# Xino_RF_v1_3.net
KiCad netlist of a schematic drawn in EAGLE
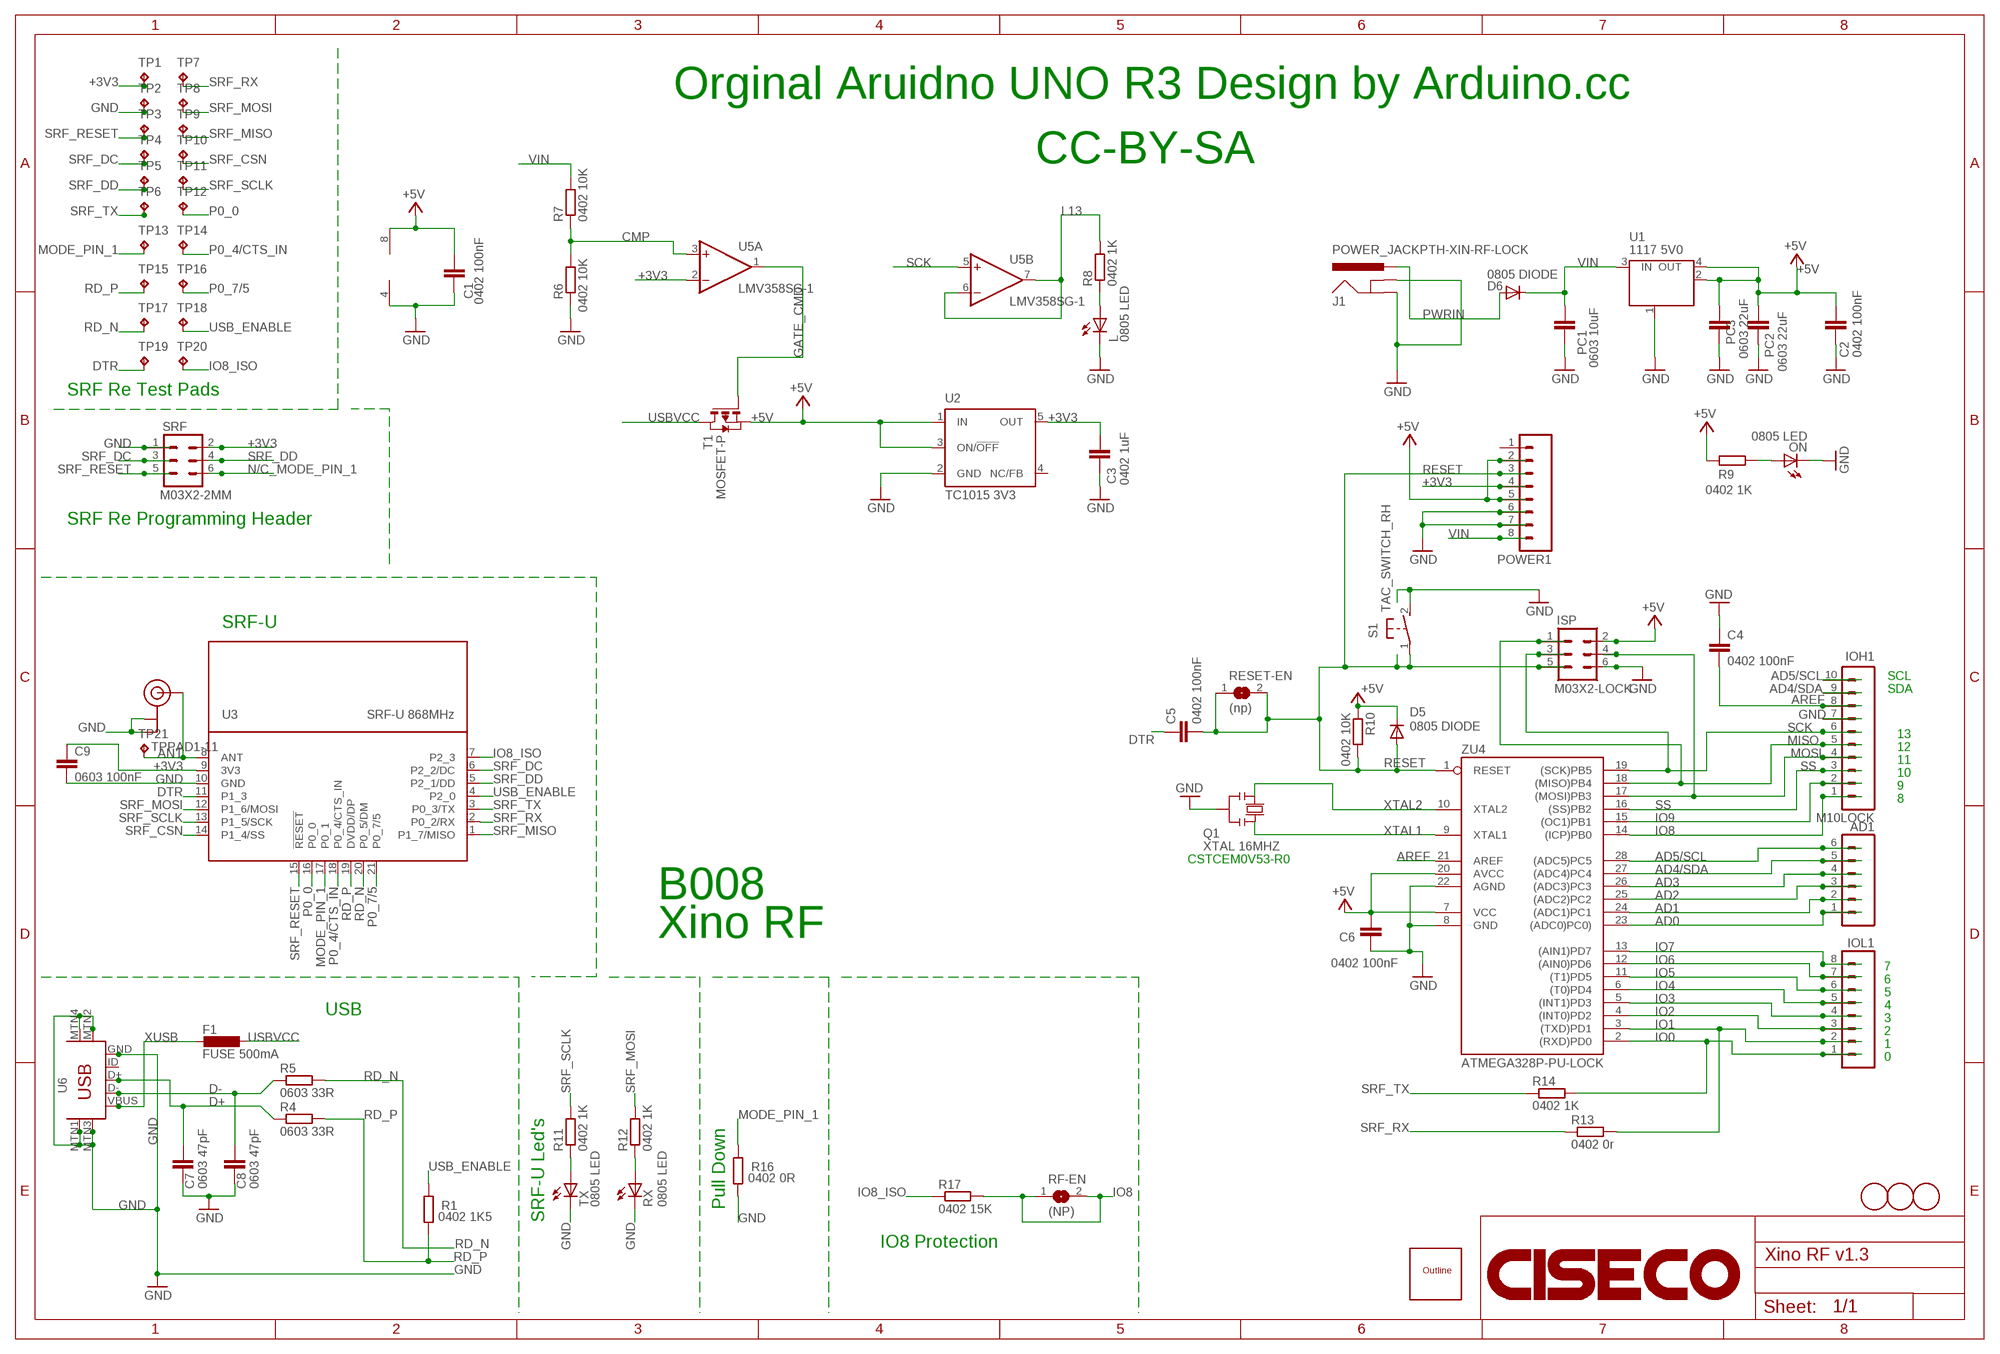
[diagram p0: schematic, sheet 1]

(export (version "E")
  (design (tool "Eeschema 10.0.6"))
  (components
    (comp (ref "AD1")
      (value "M06LOCK")
      (footprint "eagle-import:1X06_LOCK")
      (libsource (lib "eagle-import") (part "M06LOCK"))
    )
    (comp (ref "C1")
      (value "0402 100nF")
      (footprint "eagle-import:C0402-SMALLER")
      (libsource (lib "eagle-import") (part "C-EUC0402-SMALLER"))
    )
    (comp (ref "C2")
      (value "0402 100nF")
      (footprint "eagle-import:C0402-SMALLER")
      (libsource (lib "eagle-import") (part "C-EUC0402-SMALLER"))
    )
    (comp (ref "C3")
      (value "0402 1uF")
      (footprint "eagle-import:C0402-SMALLER")
      (libsource (lib "eagle-import") (part "C-EUC0402-SMALLER"))
    )
    (comp (ref "C4")
      (value "0402 100nF")
      (footprint "eagle-import:C0402-SMALLER")
      (libsource (lib "eagle-import") (part "C-EUC0402-SMALLER"))
    )
    (comp (ref "C5")
      (value "0402 100nF")
      (footprint "eagle-import:C0402-SMALLER")
      (libsource (lib "eagle-import") (part "C-EUC0402-SMALLER"))
    )
    (comp (ref "C6")
      (value "0402 100nF")
      (footprint "eagle-import:C0603-ROUND")
      (libsource (lib "eagle-import") (part "C-EU0603-RND"))
    )
    (comp (ref "C7")
      (value "0603 47pF")
      (footprint "eagle-import:C0603K-SMALL")
      (libsource (lib "eagle-import") (part "C-EUC0603K-SMALL"))
    )
    (comp (ref "C8")
      (value "0603 47pF")
      (footprint "eagle-import:C0603K-SMALL")
      (libsource (lib "eagle-import") (part "C-EUC0603K-SMALL"))
    )
    (comp (ref "C9")
      (value "0603 100nF")
      (footprint "eagle-import:C0402-SMALLER")
      (libsource (lib "eagle-import") (part "C-EUC0402-SMALLER"))
    )
    (comp (ref "D5")
      (value "0805 DIODE")
      (footprint "eagle-import:0805-DIODE")
      (libsource (lib "eagle-import") (part "DIODE-0805"))
    )
    (comp (ref "D6")
      (value "0805 DIODE")
      (footprint "eagle-import:0805-DIODE")
      (libsource (lib "eagle-import") (part "DIODE-0805"))
    )
    (comp (ref "F1")
      (value "FUSE 500mA")
      (footprint "eagle-import:L1812")
      (libsource (lib "eagle-import") (part "L-EUL1812"))
    )
    (comp (ref "FD1")
      (value "FIDUCIALMOUNT")
      (footprint "eagle-import:FIDUCIA-MOUNT")
      (libsource (lib "eagle-import") (part "FIDUCIALMOUNT"))
    )
    (comp (ref "FD2")
      (value "FIDUCIALMOUNT")
      (footprint "eagle-import:FIDUCIA-MOUNT")
      (libsource (lib "eagle-import") (part "FIDUCIALMOUNT"))
    )
    (comp (ref "FD3")
      (value "FIDUCIALMOUNT")
      (footprint "eagle-import:FIDUCIA-MOUNT")
      (libsource (lib "eagle-import") (part "FIDUCIALMOUNT"))
    )
    (comp (ref "IOH1")
      (value "M10LOCK")
      (footprint "eagle-import:1X10_LOCK")
      (libsource (lib "eagle-import") (part "M10LOCK"))
    )
    (comp (ref "IOL1")
      (value "M08LOCK")
      (footprint "eagle-import:1X08_LOCK")
      (libsource (lib "eagle-import") (part "M08LOCK"))
    )
    (comp (ref "ISP")
      (value "M03X2-LOCK")
      (footprint "eagle-import:2X3_LOCK")
      (libsource (lib "eagle-import") (part "M03X2-LOCK"))
    )
    (comp (ref "J1")
      (value "POWER_JACKPTH-XIN-RF-LOCK")
      (footprint "eagle-import:POWER_JACK_PTH_XINO_RF_LOCK")
      (libsource (lib "eagle-import") (part "POWER_JACKPTH-XIN-RF-LOCK"))
    )
    (comp (ref "L")
      (value "0805 LED")
      (footprint "eagle-import:LED-0805-1206")
      (libsource (lib "eagle-import") (part "LED0805-1206"))
    )
    (comp (ref "ON")
      (value "0805 LED")
      (footprint "eagle-import:LED-0805-1206")
      (libsource (lib "eagle-import") (part "LED0805-1206"))
    )
    (comp (ref "PC1")
      (value "0603 10uF")
      (footprint "eagle-import:C0805K")
      (libsource (lib "eagle-import") (part "C-EUC0805K"))
    )
    (comp (ref "PC2")
      (value "0603 22uF")
      (footprint "eagle-import:C0805K")
      (libsource (lib "eagle-import") (part "C-EUC0805K"))
    )
    (comp (ref "PC3")
      (value "0603 22uF")
      (footprint "eagle-import:C0805K")
      (libsource (lib "eagle-import") (part "C-EUC0805K"))
    )
    (comp (ref "POWER1")
      (value "M08LOCK")
      (footprint "eagle-import:1X08_LOCK")
      (libsource (lib "eagle-import") (part "M08LOCK"))
    )
    (comp (ref "Q1")
      (value "XTAL 16MHZ")
      (footprint "eagle-import:RESONATOR")
      (libsource (lib "eagle-import") (part "RESONATORMU"))
    )
    (comp (ref "R1")
      (value "0402 1K5")
      (footprint "eagle-import:R0402-SMALLER")
      (libsource (lib "eagle-import") (part "R-EU_R0402-SMALLER"))
    )
    (comp (ref "R4")
      (value "0603 33R")
      (footprint "eagle-import:C0603K-SMALL")
      (libsource (lib "eagle-import") (part "R-EU_0603K-SMALL"))
    )
    (comp (ref "R5")
      (value "0603 33R")
      (footprint "eagle-import:C0603K-SMALL")
      (libsource (lib "eagle-import") (part "R-EU_0603K-SMALL"))
    )
    (comp (ref "R6")
      (value "0402 10K")
      (footprint "eagle-import:R0402-SMALLER")
      (libsource (lib "eagle-import") (part "R-EU_R0402-SMALLER"))
    )
    (comp (ref "R7")
      (value "0402 10K")
      (footprint "eagle-import:R0402-SMALLER")
      (libsource (lib "eagle-import") (part "R-EU_R0402-SMALLER"))
    )
    (comp (ref "R8")
      (value "0402 1K")
      (footprint "eagle-import:R0402-SMALLER")
      (libsource (lib "eagle-import") (part "R-EU_R0402-SMALLER"))
    )
    (comp (ref "R9")
      (value "0402 1K")
      (footprint "eagle-import:R0402-SMALLER")
      (libsource (lib "eagle-import") (part "R-EU_R0402-SMALLER"))
    )
    (comp (ref "R10")
      (value "0402 10K")
      (footprint "eagle-import:R0402-SMALLER")
      (libsource (lib "eagle-import") (part "R-EU_R0402-SMALLER"))
    )
    (comp (ref "R11")
      (value "0402 1K")
      (footprint "eagle-import:R0402-SMALLER")
      (libsource (lib "eagle-import") (part "R-EU_R0402-SMALLER"))
    )
    (comp (ref "R12")
      (value "0402 1K")
      (footprint "eagle-import:R0402-SMALLER")
      (libsource (lib "eagle-import") (part "R-EU_R0402-SMALLER"))
    )
    (comp (ref "R13")
      (value "0402 0r")
      (footprint "eagle-import:R0402-SMALLER")
      (libsource (lib "eagle-import") (part "R-EU_R0402-SMALLER"))
    )
    (comp (ref "R14")
      (value "0402 1K")
      (footprint "eagle-import:R0402-SMALLER")
      (libsource (lib "eagle-import") (part "R-EU_R0402-SMALLER"))
    )
    (comp (ref "R16")
      (value "0402 0R")
      (footprint "eagle-import:R0402-SMALLER")
      (libsource (lib "eagle-import") (part "R-EU_R0402-SMALLER"))
    )
    (comp (ref "R17")
      (value "0402 15K")
      (footprint "eagle-import:R0402-SMALLER")
      (libsource (lib "eagle-import") (part "R-EU_R0402-SMALLER"))
    )
    (comp (ref "RESET-EN")
      (value "(np)")
      (footprint "eagle-import:SJ")
      (libsource (lib "eagle-import") (part "SJ"))
    )
    (comp (ref "RF-EN")
      (value "(NP)")
      (footprint "eagle-import:SJ")
      (libsource (lib "eagle-import") (part "SJ"))
    )
    (comp (ref "RX")
      (value "0805 LED")
      (footprint "eagle-import:LED-0805-1206")
      (libsource (lib "eagle-import") (part "LED0805-1206"))
    )
    (comp (ref "S1")
      (value "TAC_SWITCH_RH")
      (footprint "eagle-import:B3F-31XX")
      (libsource (lib "eagle-import") (part "TAC_SWITCH_RH"))
    )
    (comp (ref "SRF")
      (value "M03X2-2MM")
      (footprint "eagle-import:2X3_2MM")
      (libsource (lib "eagle-import") (part "M03X2-2MM"))
    )
    (comp (ref "T1")
      (value "MOSFET-P")
      (footprint "eagle-import:SOT-23")
      (libsource (lib "eagle-import") (part "PMOSSOT23"))
    )
    (comp (ref "TP1")
      (value "TPB1,27")
      (footprint "eagle-import:B1,27")
      (libsource (lib "eagle-import") (part "testpad_TPB1,27"))
    )
    (comp (ref "TP2")
      (value "TPB1,27")
      (footprint "eagle-import:B1,27")
      (libsource (lib "eagle-import") (part "testpad_TPB1,27"))
    )
    (comp (ref "TP3")
      (value "TPB1,27")
      (footprint "eagle-import:B1,27")
      (libsource (lib "eagle-import") (part "testpad_TPB1,27"))
    )
    (comp (ref "TP4")
      (value "TPB1,27")
      (footprint "eagle-import:B1,27")
      (libsource (lib "eagle-import") (part "testpad_TPB1,27"))
    )
    (comp (ref "TP5")
      (value "TPB1,27")
      (footprint "eagle-import:B1,27")
      (libsource (lib "eagle-import") (part "testpad_TPB1,27"))
    )
    (comp (ref "TP6")
      (value "TPB1,27")
      (footprint "eagle-import:B1,27")
      (libsource (lib "eagle-import") (part "testpad_TPB1,27"))
    )
    (comp (ref "TP7")
      (value "TPB1,27")
      (footprint "eagle-import:B1,27")
      (libsource (lib "eagle-import") (part "testpad_TPB1,27"))
    )
    (comp (ref "TP8")
      (value "TPB1,27")
      (footprint "eagle-import:B1,27")
      (libsource (lib "eagle-import") (part "testpad_TPB1,27"))
    )
    (comp (ref "TP9")
      (value "TPB1,27")
      (footprint "eagle-import:B1,27")
      (libsource (lib "eagle-import") (part "testpad_TPB1,27"))
    )
    (comp (ref "TP10")
      (value "TPB1,27")
      (footprint "eagle-import:B1,27")
      (libsource (lib "eagle-import") (part "testpad_TPB1,27"))
    )
    (comp (ref "TP11")
      (value "TPB1,27")
      (footprint "eagle-import:B1,27")
      (libsource (lib "eagle-import") (part "testpad_TPB1,27"))
    )
    (comp (ref "TP12")
      (value "TPB1,27")
      (footprint "eagle-import:B1,27")
      (libsource (lib "eagle-import") (part "testpad_TPB1,27"))
    )
    (comp (ref "TP13")
      (value "TPB1,27")
      (footprint "eagle-import:B1,27")
      (libsource (lib "eagle-import") (part "testpad_TPB1,27"))
    )
    (comp (ref "TP14")
      (value "TPB1,27")
      (footprint "eagle-import:B1,27")
      (libsource (lib "eagle-import") (part "testpad_TPB1,27"))
    )
    (comp (ref "TP15")
      (value "TPB1,27")
      (footprint "eagle-import:B1,27")
      (libsource (lib "eagle-import") (part "testpad_TPB1,27"))
    )
    (comp (ref "TP16")
      (value "TPB1,27")
      (footprint "eagle-import:B1,27")
      (libsource (lib "eagle-import") (part "testpad_TPB1,27"))
    )
    (comp (ref "TP17")
      (value "TPB1,27")
      (footprint "eagle-import:B1,27")
      (libsource (lib "eagle-import") (part "testpad_TPB1,27"))
    )
    (comp (ref "TP18")
      (value "TPB1,27")
      (footprint "eagle-import:B1,27")
      (libsource (lib "eagle-import") (part "testpad_TPB1,27"))
    )
    (comp (ref "TP19")
      (value "TPB1,27")
      (footprint "eagle-import:B1,27")
      (libsource (lib "eagle-import") (part "testpad_TPB1,27"))
    )
    (comp (ref "TP20")
      (value "TPB1,27")
      (footprint "eagle-import:B1,27")
      (libsource (lib "eagle-import") (part "testpad_TPB1,27"))
    )
    (comp (ref "TP21")
      (value "TPPAD1-11")
      (footprint "eagle-import:P1-11")
      (libsource (lib "eagle-import") (part "TPPAD1-11"))
    )
    (comp (ref "TX")
      (value "0805 LED")
      (footprint "eagle-import:LED-0805-1206")
      (libsource (lib "eagle-import") (part "LED0805-1206"))
    )
    (comp (ref "U$1")
      (value "CISECO-MEDIUM")
      (footprint "eagle-import:CISECO-1.3MM")
      (libsource (lib "eagle-import") (part "CISECO-MEDIUM"))
    )
    (comp (ref "U$2")
      (value "ARDUINO-OUTLINE-MILL")
      (footprint "eagle-import:ARDUINO-OUTLINE-MILL")
      (libsource (lib "eagle-import") (part "ARDUINO-OUTLINE-MILL"))
    )
    (comp (ref "U$3")
      (value "CISECO-LARGE")
      (footprint "eagle-import:CISECO-4MM")
      (libsource (lib "eagle-import") (part "CISECO-LARGE"))
    )
    (comp (ref "U1")
      (value "1117 5V0")
      (footprint "eagle-import:SOT223")
      (libsource (lib "eagle-import") (part "MC33269ST-3.3T3"))
    )
    (comp (ref "U2")
      (value "TC1015 3V3")
      (footprint "eagle-import:SOT23-DBV")
      (libsource (lib "eagle-import") (part "LP2985-XXDBVR33"))
    )
    (comp (ref "U3")
      (value "SRF-U 868MHz")
      (footprint "eagle-import:SRF-LANDING-1.2")
      (libsource (lib "eagle-import") (part "SRF-LANDING-1.2"))
    )
    (comp (ref "U5")
      (value "LMV358SG-1")
      (footprint "eagle-import:SO08")
      (libsource (lib "eagle-import") (part "LMV358?MX"))
    )
    (comp (ref "U6")
      (value "USB-MINIB-5PIN")
      (footprint "eagle-import:USB-MINIB-CISECO-1")
      (libsource (lib "eagle-import") (part "USB-MINIB-5PIN-TWEAKED"))
    )
    (comp (ref "U11")
      (value "U.FL 868")
      (footprint "eagle-import:U.FL")
      (libsource (lib "eagle-import") (part "U.FL"))
    )
    (comp (ref "ZU4")
      (value "ATMEGA328P-PU-LOCK")
      (footprint "eagle-import:DIL28-3-LOCK")
      (libsource (lib "eagle-import") (part "ATMEGA328P-PU-LOCK"))
    )
  )
  (nets
    (net (code "1") (name "+5V") (class "Default")
      (node (ref "C1") (pin "2") (pinfunction "2_2") (pintype "passive"))
      (node (ref "C2") (pin "2") (pinfunction "2_2") (pintype "passive"))
      (node (ref "C6") (pin "2") (pinfunction "2_2") (pintype "passive"))
      (node (ref "D5") (pin "C") (pinfunction "C_C") (pintype "passive"))
      (node (ref "ISP") (pin "2") (pinfunction "2_2") (pintype "passive"))
      (node (ref "PC2") (pin "1") (pinfunction "1_1") (pintype "passive"))
      (node (ref "PC3") (pin "1") (pinfunction "1_1") (pintype "passive"))
      (node (ref "POWER1") (pin "2") (pinfunction "2_2") (pintype "passive"))
      (node (ref "POWER1") (pin "5") (pinfunction "5_5") (pintype "passive"))
      (node (ref "R10") (pin "1") (pinfunction "1_1") (pintype "passive"))
      (node (ref "R9") (pin "2") (pinfunction "2_2") (pintype "passive"))
      (node (ref "T1") (pin "2") (pinfunction "S_2") (pintype "passive"))
      (node (ref "U1") (pin "2") (pinfunction "OUT_2") (pintype "passive"))
      (node (ref "U1") (pin "4") (pinfunction "OUT_4") (pintype "passive"))
      (node (ref "U2") (pin "1") (pinfunction "IN_1") (pintype "input"))
      (node (ref "U2") (pin "3") (pinfunction "ON/~{OFF}_3") (pintype "input"))
      (node (ref "U5") (pin "8") (pinfunction "V+_8") (pintype "power_in"))
      (node (ref "ZU4") (pin "20") (pinfunction "AVCC_20") (pintype "power_in"))
      (node (ref "ZU4") (pin "7") (pinfunction "VCC_7") (pintype "power_in"))
    )
    (net (code "2") (name "/+3V3") (class "Default")
      (node (ref "C3") (pin "2") (pinfunction "2_2") (pintype "passive"))
      (node (ref "C9") (pin "1") (pinfunction "1_1") (pintype "passive"))
      (node (ref "POWER1") (pin "4") (pinfunction "4_4") (pintype "passive"))
      (node (ref "SRF") (pin "2") (pinfunction "2_2") (pintype "passive"))
      (node (ref "TP1") (pin "TP") (pinfunction "TP_TP") (pintype "input"))
      (node (ref "U2") (pin "5") (pinfunction "OUT_5") (pintype "passive"))
      (node (ref "U3") (pin "9") (pinfunction "3V3_9") (pintype "power_in"))
      (node (ref "U5") (pin "2") (pinfunction "-IN_2") (pintype "input"))
    )
    (net (code "3") (name "/AD0") (class "Default")
      (node (ref "AD1") (pin "1") (pinfunction "1_1") (pintype "passive"))
      (node (ref "ZU4") (pin "23") (pinfunction "(ADC0)PC0)_23") (pintype "bidirectional"))
    )
    (net (code "4") (name "/AD1") (class "Default")
      (node (ref "AD1") (pin "2") (pinfunction "2_2") (pintype "passive"))
      (node (ref "ZU4") (pin "24") (pinfunction "(ADC1)PC1_24") (pintype "bidirectional"))
    )
    (net (code "5") (name "/AD2") (class "Default")
      (node (ref "AD1") (pin "3") (pinfunction "3_3") (pintype "passive"))
      (node (ref "ZU4") (pin "25") (pinfunction "(ADC2)PC2_25") (pintype "bidirectional"))
    )
    (net (code "6") (name "/AD3") (class "Default")
      (node (ref "AD1") (pin "4") (pinfunction "4_4") (pintype "passive"))
      (node (ref "ZU4") (pin "26") (pinfunction "(ADC3)PC3_26") (pintype "bidirectional"))
    )
    (net (code "7") (name "/AD4{slash}SDA") (class "Default")
      (node (ref "AD1") (pin "5") (pinfunction "5_5") (pintype "passive"))
      (node (ref "IOH1") (pin "9") (pinfunction "9_9") (pintype "passive"))
      (node (ref "ZU4") (pin "27") (pinfunction "(ADC4)PC4_27") (pintype "bidirectional"))
    )
    (net (code "8") (name "/AD5{slash}SCL") (class "Default")
      (node (ref "AD1") (pin "6") (pinfunction "6_6") (pintype "passive"))
      (node (ref "IOH1") (pin "10") (pinfunction "10_10") (pintype "passive"))
      (node (ref "ZU4") (pin "28") (pinfunction "(ADC5)PC5_28") (pintype "bidirectional"))
    )
    (net (code "9") (name "/ANT") (class "Default")
      (node (ref "TP21") (pin "TP") (pinfunction "TP_TP") (pintype "input"))
      (node (ref "U11") (pin "P$3") (pinfunction "SIGNAL_P$3") (pintype "bidirectional"))
      (node (ref "U3") (pin "8") (pinfunction "ANT_8") (pintype "output"))
    )
    (net (code "10") (name "/AREF") (class "Default")
      (node (ref "C4") (pin "2") (pinfunction "2_2") (pintype "passive"))
      (node (ref "IOH1") (pin "8") (pinfunction "8_8") (pintype "passive"))
      (node (ref "ZU4") (pin "21") (pinfunction "AREF_21") (pintype "passive"))
    )
    (net (code "11") (name "/CMP") (class "Default")
      (node (ref "R6") (pin "2") (pinfunction "2_2") (pintype "passive"))
      (node (ref "R7") (pin "1") (pinfunction "1_1") (pintype "passive"))
      (node (ref "U5") (pin "3") (pinfunction "+IN_3") (pintype "input"))
    )
    (net (code "12") (name "/D+") (class "Default")
      (node (ref "C7") (pin "1") (pinfunction "1_1") (pintype "passive"))
      (node (ref "R4") (pin "1") (pinfunction "1_1") (pintype "passive"))
      (node (ref "U6") (pin "D+") (pinfunction "D+_D+") (pintype "bidirectional"))
    )
    (net (code "13") (name "/D-") (class "Default")
      (node (ref "C8") (pin "1") (pinfunction "1_1") (pintype "passive"))
      (node (ref "R5") (pin "1") (pinfunction "1_1") (pintype "passive"))
      (node (ref "U6") (pin "D-") (pinfunction "D-_D-") (pintype "bidirectional"))
    )
    (net (code "14") (name "/DTR") (class "Default")
      (node (ref "C5") (pin "1") (pinfunction "1_1") (pintype "passive"))
      (node (ref "TP19") (pin "TP") (pinfunction "TP_TP") (pintype "input"))
      (node (ref "U3") (pin "11") (pinfunction "P1_3_11") (pintype "bidirectional"))
    )
    (net (code "15") (name "/GATE_CMD") (class "Default")
      (node (ref "T1") (pin "3") (pinfunction "G_3") (pintype "passive"))
      (node (ref "U5") (pin "1") (pinfunction "OUT_1") (pintype "output"))
    )
    (net (code "16") (name "/IO0") (class "Default")
      (node (ref "IOL1") (pin "1") (pinfunction "1_1") (pintype "passive"))
      (node (ref "R14") (pin "2") (pinfunction "2_2") (pintype "passive"))
      (node (ref "ZU4") (pin "2") (pinfunction "(RXD)PD0_2") (pintype "bidirectional"))
    )
    (net (code "17") (name "/IO1") (class "Default")
      (node (ref "IOL1") (pin "2") (pinfunction "2_2") (pintype "passive"))
      (node (ref "R13") (pin "2") (pinfunction "2_2") (pintype "passive"))
      (node (ref "ZU4") (pin "3") (pinfunction "(TXD)PD1_3") (pintype "bidirectional"))
    )
    (net (code "18") (name "/IO2") (class "Default")
      (node (ref "IOL1") (pin "3") (pinfunction "3_3") (pintype "passive"))
      (node (ref "ZU4") (pin "4") (pinfunction "(INT0)PD2_4") (pintype "bidirectional"))
    )
    (net (code "19") (name "/IO3") (class "Default")
      (node (ref "IOL1") (pin "4") (pinfunction "4_4") (pintype "passive"))
      (node (ref "ZU4") (pin "5") (pinfunction "(INT1)PD3_5") (pintype "bidirectional"))
    )
    (net (code "20") (name "/IO4") (class "Default")
      (node (ref "IOL1") (pin "5") (pinfunction "5_5") (pintype "passive"))
      (node (ref "ZU4") (pin "6") (pinfunction "(T0)PD4_6") (pintype "bidirectional"))
    )
    (net (code "21") (name "/IO5") (class "Default")
      (node (ref "IOL1") (pin "6") (pinfunction "6_6") (pintype "passive"))
      (node (ref "ZU4") (pin "11") (pinfunction "(T1)PD5_11") (pintype "bidirectional"))
    )
    (net (code "22") (name "/IO6") (class "Default")
      (node (ref "IOL1") (pin "7") (pinfunction "7_7") (pintype "passive"))
      (node (ref "ZU4") (pin "12") (pinfunction "(AIN0)PD6_12") (pintype "bidirectional"))
    )
    (net (code "23") (name "/IO7") (class "Default")
      (node (ref "IOL1") (pin "8") (pinfunction "8_8") (pintype "passive"))
      (node (ref "ZU4") (pin "13") (pinfunction "(AIN1)PD7_13") (pintype "bidirectional"))
    )
    (net (code "24") (name "/IO8") (class "Default")
      (node (ref "IOH1") (pin "1") (pinfunction "1_1") (pintype "passive"))
      (node (ref "R17") (pin "2") (pinfunction "2_2") (pintype "passive"))
      (node (ref "RF-EN") (pin "1") (pinfunction "1_1") (pintype "passive"))
      (node (ref "RF-EN") (pin "2") (pinfunction "2_2") (pintype "passive"))
      (node (ref "ZU4") (pin "14") (pinfunction "(ICP)PB0_14") (pintype "bidirectional"))
    )
    (net (code "25") (name "/IO8_ISO") (class "Default")
      (node (ref "R17") (pin "1") (pinfunction "1_1") (pintype "passive"))
      (node (ref "TP20") (pin "TP") (pinfunction "TP_TP") (pintype "input"))
      (node (ref "U3") (pin "7") (pinfunction "P2_3_7") (pintype "bidirectional"))
    )
    (net (code "26") (name "/IO9") (class "Default")
      (node (ref "IOH1") (pin "2") (pinfunction "2_2") (pintype "passive"))
      (node (ref "ZU4") (pin "15") (pinfunction "(OC1)PB1_15") (pintype "bidirectional"))
    )
    (net (code "27") (name "/L13") (class "Default")
      (node (ref "R8") (pin "2") (pinfunction "2_2") (pintype "passive"))
      (node (ref "U5") (pin "6") (pinfunction "-IN_6") (pintype "input"))
      (node (ref "U5") (pin "7") (pinfunction "OUT_7") (pintype "output"))
    )
    (net (code "28") (name "/MISO") (class "Default")
      (node (ref "IOH1") (pin "5") (pinfunction "5_5") (pintype "passive"))
      (node (ref "ISP") (pin "1") (pinfunction "1_1") (pintype "passive"))
      (node (ref "ZU4") (pin "18") (pinfunction "(MISO)PB4_18") (pintype "bidirectional"))
    )
    (net (code "29") (name "/MODE_PIN_1") (class "Default")
      (node (ref "R16") (pin "2") (pinfunction "2_2") (pintype "passive"))
      (node (ref "TP13") (pin "TP") (pinfunction "TP_TP") (pintype "input"))
      (node (ref "U3") (pin "17") (pinfunction "P0_1_17") (pintype "bidirectional"))
    )
    (net (code "30") (name "/MOSI") (class "Default")
      (node (ref "IOH1") (pin "4") (pinfunction "4_4") (pintype "passive"))
      (node (ref "ISP") (pin "4") (pinfunction "4_4") (pintype "passive"))
      (node (ref "ZU4") (pin "17") (pinfunction "(MOSI)PB3_17") (pintype "bidirectional"))
    )
    (net (code "31") (name "/N{slash}C_MODE_PIN_1") (class "Default")
      (node (ref "SRF") (pin "6") (pinfunction "6_6") (pintype "passive"))
    )
    (net (code "32") (name "/P0_0") (class "Default")
      (node (ref "TP12") (pin "TP") (pinfunction "TP_TP") (pintype "input"))
      (node (ref "U3") (pin "16") (pinfunction "P0_0_16") (pintype "bidirectional"))
    )
    (net (code "33") (name "/P0_4{slash}CTS_IN") (class "Default")
      (node (ref "TP14") (pin "TP") (pinfunction "TP_TP") (pintype "input"))
      (node (ref "U3") (pin "18") (pinfunction "P0_4/CTS_IN_18") (pintype "bidirectional"))
    )
    (net (code "34") (name "/P0_7{slash}5") (class "Default")
      (node (ref "TP16") (pin "TP") (pinfunction "TP_TP") (pintype "input"))
      (node (ref "U3") (pin "21") (pinfunction "P0_7/5_21") (pintype "bidirectional"))
    )
    (net (code "35") (name "/PWRIN") (class "Default")
      (node (ref "D6") (pin "A") (pinfunction "A_A") (pintype "passive"))
      (node (ref "J1") (pin "PWR") (pinfunction "PWR_PWR") (pintype "bidirectional"))
    )
    (net (code "36") (name "/RD_N") (class "Default")
      (node (ref "R5") (pin "2") (pinfunction "2_2") (pintype "passive"))
      (node (ref "TP17") (pin "TP") (pinfunction "TP_TP") (pintype "input"))
      (node (ref "U3") (pin "20") (pinfunction "P0_5/DM_20") (pintype "bidirectional"))
    )
    (net (code "37") (name "/RD_P") (class "Default")
      (node (ref "R1") (pin "1") (pinfunction "1_1") (pintype "passive"))
      (node (ref "R4") (pin "2") (pinfunction "2_2") (pintype "passive"))
      (node (ref "TP15") (pin "TP") (pinfunction "TP_TP") (pintype "input"))
      (node (ref "U3") (pin "19") (pinfunction "DVDD/DP_19") (pintype "bidirectional"))
    )
    (net (code "38") (name "/RESET") (class "Default")
      (node (ref "C5") (pin "2") (pinfunction "2_2") (pintype "passive"))
      (node (ref "D5") (pin "A") (pinfunction "A_A") (pintype "passive"))
      (node (ref "ISP") (pin "5") (pinfunction "5_5") (pintype "passive"))
      (node (ref "POWER1") (pin "3") (pinfunction "3_3") (pintype "passive"))
      (node (ref "R10") (pin "2") (pinfunction "2_2") (pintype "passive"))
      (node (ref "RESET-EN") (pin "1") (pinfunction "1_1") (pintype "passive"))
      (node (ref "RESET-EN") (pin "2") (pinfunction "2_2") (pintype "passive"))
      (node (ref "S1") (pin "1") (pinfunction "P_1") (pintype "passive"))
      (node (ref "ZU4") (pin "1") (pinfunction "RESET_1") (pintype "input"))
    )
    (net (code "39") (name "/SCK") (class "Default")
      (node (ref "IOH1") (pin "6") (pinfunction "6_6") (pintype "passive"))
      (node (ref "ISP") (pin "3") (pinfunction "3_3") (pintype "passive"))
      (node (ref "U5") (pin "5") (pinfunction "+IN_5") (pintype "input"))
      (node (ref "ZU4") (pin "19") (pinfunction "(SCK)PB5_19") (pintype "bidirectional"))
    )
    (net (code "40") (name "/SRF_CSN") (class "Default")
      (node (ref "TP10") (pin "TP") (pinfunction "TP_TP") (pintype "input"))
      (node (ref "U3") (pin "14") (pinfunction "P1_4/SS_14") (pintype "bidirectional"))
    )
    (net (code "41") (name "/SRF_DC") (class "Default")
      (node (ref "SRF") (pin "3") (pinfunction "3_3") (pintype "passive"))
      (node (ref "TP4") (pin "TP") (pinfunction "TP_TP") (pintype "input"))
      (node (ref "U3") (pin "6") (pinfunction "P2_2/DC_6") (pintype "bidirectional"))
    )
    (net (code "42") (name "/SRF_DD") (class "Default")
      (node (ref "SRF") (pin "4") (pinfunction "4_4") (pintype "passive"))
      (node (ref "TP5") (pin "TP") (pinfunction "TP_TP") (pintype "input"))
      (node (ref "U3") (pin "5") (pinfunction "P2_1/DD_5") (pintype "bidirectional"))
    )
    (net (code "43") (name "/SRF_MISO") (class "Default")
      (node (ref "TP9") (pin "TP") (pinfunction "TP_TP") (pintype "input"))
      (node (ref "U3") (pin "1") (pinfunction "P1_7/MISO_1") (pintype "bidirectional"))
    )
    (net (code "44") (name "/SRF_MOSI") (class "Default")
      (node (ref "R12") (pin "2") (pinfunction "2_2") (pintype "passive"))
      (node (ref "TP8") (pin "TP") (pinfunction "TP_TP") (pintype "input"))
      (node (ref "U3") (pin "12") (pinfunction "P1_6/MOSI_12") (pintype "bidirectional"))
    )
    (net (code "45") (name "/SRF_RESET") (class "Default")
      (node (ref "SRF") (pin "5") (pinfunction "5_5") (pintype "passive"))
      (node (ref "TP3") (pin "TP") (pinfunction "TP_TP") (pintype "input"))
      (node (ref "U3") (pin "15") (pinfunction "~{RESET}_15") (pintype "input"))
    )
    (net (code "46") (name "/SRF_RX") (class "Default")
      (node (ref "R13") (pin "1") (pinfunction "1_1") (pintype "passive"))
      (node (ref "TP7") (pin "TP") (pinfunction "TP_TP") (pintype "input"))
      (node (ref "U3") (pin "2") (pinfunction "P0_2/RX_2") (pintype "bidirectional"))
    )
    (net (code "47") (name "/SRF_SCLK") (class "Default")
      (node (ref "R11") (pin "2") (pinfunction "2_2") (pintype "passive"))
      (node (ref "TP11") (pin "TP") (pinfunction "TP_TP") (pintype "input"))
      (node (ref "U3") (pin "13") (pinfunction "P1_5/SCK_13") (pintype "bidirectional"))
    )
    (net (code "48") (name "/SRF_TX") (class "Default")
      (node (ref "R14") (pin "1") (pinfunction "1_1") (pintype "passive"))
      (node (ref "TP6") (pin "TP") (pinfunction "TP_TP") (pintype "input"))
      (node (ref "U3") (pin "3") (pinfunction "P0_3/TX_3") (pintype "bidirectional"))
    )
    (net (code "49") (name "/SS") (class "Default")
      (node (ref "IOH1") (pin "3") (pinfunction "3_3") (pintype "passive"))
      (node (ref "ZU4") (pin "16") (pinfunction "(SS)PB2_16") (pintype "bidirectional"))
    )
    (net (code "50") (name "/USBVCC") (class "Default")
      (node (ref "F1") (pin "1") (pinfunction "1_1") (pintype "passive"))
      (node (ref "T1") (pin "1") (pinfunction "D_1") (pintype "passive"))
    )
    (net (code "51") (name "/USB_ENABLE") (class "Default")
      (node (ref "R1") (pin "2") (pinfunction "2_2") (pintype "passive"))
      (node (ref "TP18") (pin "TP") (pinfunction "TP_TP") (pintype "input"))
      (node (ref "U3") (pin "4") (pinfunction "P2_0_4") (pintype "bidirectional"))
    )
    (net (code "52") (name "/VIN") (class "Default")
      (node (ref "D6") (pin "C") (pinfunction "C_C") (pintype "passive"))
      (node (ref "PC1") (pin "1") (pinfunction "1_1") (pintype "passive"))
      (node (ref "POWER1") (pin "8") (pinfunction "8_8") (pintype "passive"))
      (node (ref "R7") (pin "2") (pinfunction "2_2") (pintype "passive"))
      (node (ref "U1") (pin "3") (pinfunction "IN_3") (pintype "input"))
    )
    (net (code "53") (name "/XTAL1") (class "Default")
      (node (ref "Q1") (pin "3") (pinfunction "3_3") (pintype "passive"))
      (node (ref "ZU4") (pin "9") (pinfunction "XTAL1_9") (pintype "bidirectional"))
    )
    (net (code "54") (name "/XTAL2") (class "Default")
      (node (ref "Q1") (pin "1") (pinfunction "1_1") (pintype "passive"))
      (node (ref "ZU4") (pin "10") (pinfunction "XTAL2_10") (pintype "bidirectional"))
    )
    (net (code "55") (name "/XUSB") (class "Default")
      (node (ref "F1") (pin "2") (pinfunction "2_2") (pintype "passive"))
      (node (ref "U6") (pin "VBUS") (pinfunction "VBUS_VBUS") (pintype "bidirectional"))
    )
    (net (code "56") (name "GND") (class "Default")
      (node (ref "C1") (pin "1") (pinfunction "1_1") (pintype "passive"))
      (node (ref "C2") (pin "1") (pinfunction "1_1") (pintype "passive"))
      (node (ref "C3") (pin "1") (pinfunction "1_1") (pintype "passive"))
      (node (ref "C4") (pin "1") (pinfunction "1_1") (pintype "passive"))
      (node (ref "C6") (pin "1") (pinfunction "1_1") (pintype "passive"))
      (node (ref "C7") (pin "2") (pinfunction "2_2") (pintype "passive"))
      (node (ref "C8") (pin "2") (pinfunction "2_2") (pintype "passive"))
      (node (ref "C9") (pin "2") (pinfunction "2_2") (pintype "passive"))
      (node (ref "IOH1") (pin "7") (pinfunction "7_7") (pintype "passive"))
      (node (ref "ISP") (pin "6") (pinfunction "6_6") (pintype "passive"))
      (node (ref "J1") (pin "GND") (pinfunction "GND_GND") (pintype "bidirectional"))
      (node (ref "J1") (pin "GNDBREAK") (pinfunction "GNDBREAK_GNDBREAK") (pintype "bidirectional"))
      (node (ref "L") (pin "C") (pinfunction "C_C") (pintype "passive"))
      (node (ref "ON") (pin "C") (pinfunction "C_C") (pintype "passive"))
      (node (ref "PC1") (pin "2") (pinfunction "2_2") (pintype "passive"))
      (node (ref "PC2") (pin "2") (pinfunction "2_2") (pintype "passive"))
      (node (ref "PC3") (pin "2") (pinfunction "2_2") (pintype "passive"))
      (node (ref "POWER1") (pin "6") (pinfunction "6_6") (pintype "passive"))
      (node (ref "POWER1") (pin "7") (pinfunction "7_7") (pintype "passive"))
      (node (ref "Q1") (pin "2") (pinfunction "2_2") (pintype "passive"))
      (node (ref "R16") (pin "1") (pinfunction "1_1") (pintype "passive"))
      (node (ref "R6") (pin "1") (pinfunction "1_1") (pintype "passive"))
      (node (ref "RX") (pin "C") (pinfunction "C_C") (pintype "passive"))
      (node (ref "S1") (pin "2") (pinfunction "S_2") (pintype "passive"))
      (node (ref "SRF") (pin "1") (pinfunction "1_1") (pintype "passive"))
      (node (ref "TP2") (pin "TP") (pinfunction "TP_TP") (pintype "input"))
      (node (ref "TX") (pin "C") (pinfunction "C_C") (pintype "passive"))
      (node (ref "U1") (pin "1") (pinfunction "GND/ADJ_1") (pintype "input"))
      (node (ref "U11") (pin "P$1") (pinfunction "GND_P$1") (pintype "bidirectional"))
      (node (ref "U11") (pin "P$2") (pinfunction "GND_P$2") (pintype "bidirectional"))
      (node (ref "U2") (pin "2") (pinfunction "GND_2") (pintype "power_in"))
      (node (ref "U3") (pin "10") (pinfunction "GND_10") (pintype "power_in"))
      (node (ref "U5") (pin "4") (pinfunction "V-_4") (pintype "power_in"))
      (node (ref "U6") (pin "GND") (pinfunction "GND_GND") (pintype "bidirectional"))
      (node (ref "U6") (pin "MTN1") (pinfunction "MTN2_MTN1") (pintype "bidirectional"))
      (node (ref "U6") (pin "MTN2") (pinfunction "MTN3_MTN2") (pintype "bidirectional"))
      (node (ref "U6") (pin "MTN3") (pinfunction "MTN1_MTN3") (pintype "bidirectional"))
      (node (ref "U6") (pin "MTN4") (pinfunction "MTN4_MTN4") (pintype "bidirectional"))
      (node (ref "ZU4") (pin "22") (pinfunction "AGND_22") (pintype "power_in"))
      (node (ref "ZU4") (pin "8") (pinfunction "GND_8") (pintype "power_in"))
    )
    (net (code "57") (name "Net-(L-PadA)") (class "Default")
      (node (ref "L") (pin "A") (pinfunction "A_A") (pintype "passive"))
      (node (ref "R8") (pin "1") (pinfunction "1_1") (pintype "passive"))
    )
    (net (code "58") (name "Net-(ON-PadA)") (class "Default")
      (node (ref "ON") (pin "A") (pinfunction "A_A") (pintype "passive"))
      (node (ref "R9") (pin "1") (pinfunction "1_1") (pintype "passive"))
    )
    (net (code "59") (name "Net-(R11-Pad1)") (class "Default")
      (node (ref "R11") (pin "1") (pinfunction "1_1") (pintype "passive"))
      (node (ref "TX") (pin "A") (pinfunction "A_A") (pintype "passive"))
    )
    (net (code "60") (name "Net-(R12-Pad1)") (class "Default")
      (node (ref "R12") (pin "1") (pinfunction "1_1") (pintype "passive"))
      (node (ref "RX") (pin "A") (pinfunction "A_A") (pintype "passive"))
    )
    (net (code "61") (name "unconnected-(POWER1-Pad1)") (class "Default")
      (node (ref "POWER1") (pin "1") (pinfunction "1_1") (pintype "passive"))
    )
    (net (code "62") (name "unconnected-(U2-NC{slash}FB-Pad4)") (class "Default")
      (node (ref "U2") (pin "4") (pinfunction "NC/FB_4") (pintype "passive"))
    )
    (net (code "63") (name "unconnected-(U6-PadID)") (class "Default")
      (node (ref "U6") (pin "ID") (pinfunction "ID_ID") (pintype "bidirectional"))
    )
  )
)
